# design.net
KiCad netlist of a schematic drawn in Altium Designer
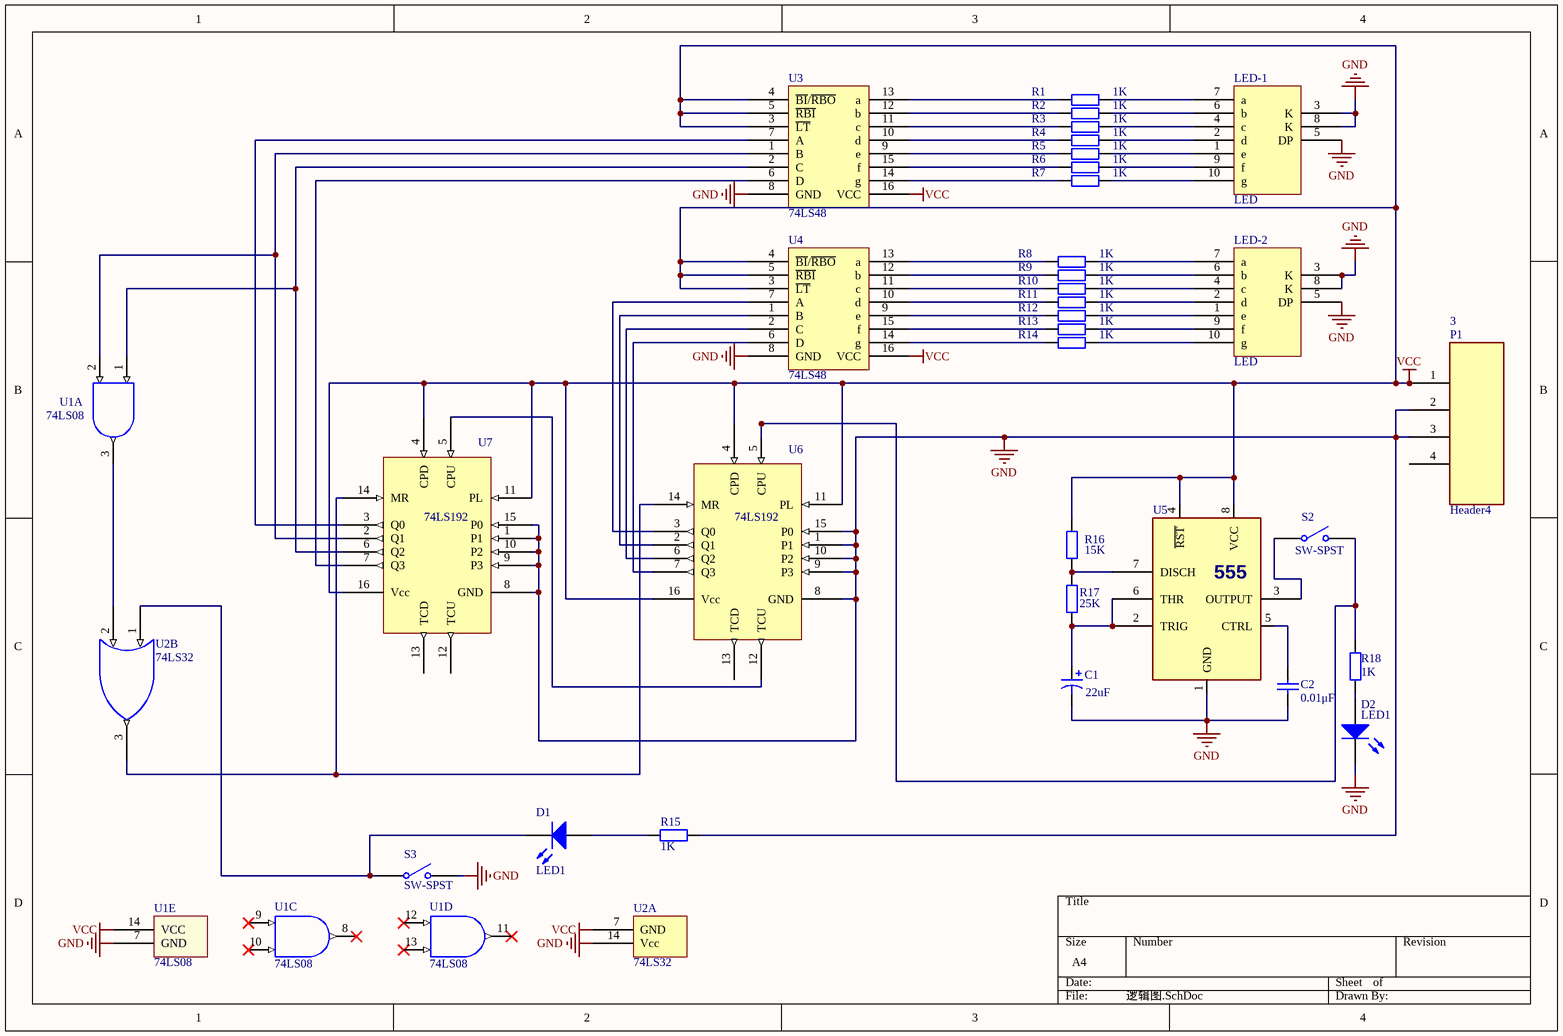
[diagram p0: 逻辑图.SchDoc]

(export (version "E")
  (design (tool "Eeschema 10.0.6"))
  (components
    (comp (ref "3")
      (value "~")
      (footprint "SIP4")
      (description "555 Timer, General-Purpose Single Bipolar Timer")
      (fields (field (name "MANF_P#") "NE555P, NE555PE4") (field (name "MANF") "Texas Instruments"))
      (libsource (lib "ne555") (part "NE555_DIP8"))
    )
    (comp (ref "C1")
      (value "22uF")
      (footprint "RB.2/.4")
      (description "Polarized Capacitor (Radial)")
      (fields (field (name "Comment") "Cap Pol1") (field (name "PUBLISHER") "Altium Limited"))
      (libsource (lib "Miscellaneous Devices") (part "Cap Pol1"))
    )
    (comp (ref "C2")
      (value "0.01μF")
      (footprint "RAD0.2")
      (description "Capacitor")
      (fields (field (name "PUBLISHER") "Altium Limited"))
      (libsource (lib "Miscellaneous Devices") (part "Cap"))
    )
    (comp (ref "D1")
      (value "LED1")
      (footprint "LED-1")
      (description "Typical RED GaAs LED")
      (fields (field (name "PUBLISHER") "Altium Limited"))
      (libsource (lib "Miscellaneous Devices") (part "LED1"))
    )
    (comp (ref "D2")
      (value "LED1")
      (footprint "RAD0.1")
      (description "Typical RED GaAs LED")
      (fields (field (name "PUBLISHER") "Altium Limited"))
      (libsource (lib "Miscellaneous Devices") (part "LED1"))
    )
    (comp (ref "LED-1")
      (value "LED")
      (footprint "DPY_10-SEG_DP(LED)")
      (libsource (lib "Schlib1") (part "LED"))
    )
    (comp (ref "LED-2")
      (value "LED")
      (footprint "DPY_10-SEG_DP(LED)")
      (libsource (lib "Schlib1") (part "LED"))
    )
    (comp (ref "R1")
      (value "1K")
      (footprint "AXIAL-0.4")
      (description "Resistor")
      (fields (field (name "PUBLISHER") "Altium Limited"))
      (libsource (lib "Miscellaneous Devices") (part "Res2"))
    )
    (comp (ref "R2")
      (value "1K")
      (footprint "AXIAL-0.4")
      (description "Resistor")
      (fields (field (name "PUBLISHER") "Altium Limited"))
      (libsource (lib "Miscellaneous Devices") (part "Res2"))
    )
    (comp (ref "R3")
      (value "1K")
      (footprint "AXIAL-0.4")
      (description "Resistor")
      (fields (field (name "PUBLISHER") "Altium Limited"))
      (libsource (lib "Miscellaneous Devices") (part "Res2"))
    )
    (comp (ref "R4")
      (value "1K")
      (footprint "AXIAL-0.4")
      (description "Resistor")
      (fields (field (name "PUBLISHER") "Altium Limited"))
      (libsource (lib "Miscellaneous Devices") (part "Res2"))
    )
    (comp (ref "R5")
      (value "1K")
      (footprint "AXIAL-0.4")
      (description "Resistor")
      (fields (field (name "PUBLISHER") "Altium Limited"))
      (libsource (lib "Miscellaneous Devices") (part "Res2"))
    )
    (comp (ref "R6")
      (value "1K")
      (footprint "AXIAL-0.4")
      (description "Resistor")
      (fields (field (name "PUBLISHER") "Altium Limited"))
      (libsource (lib "Miscellaneous Devices") (part "Res2"))
    )
    (comp (ref "R7")
      (value "1K")
      (footprint "AXIAL-0.4")
      (description "Resistor")
      (fields (field (name "PUBLISHER") "Altium Limited"))
      (libsource (lib "Miscellaneous Devices") (part "Res2"))
    )
    (comp (ref "R8")
      (value "1K")
      (footprint "AXIAL-0.4")
      (description "Resistor")
      (fields (field (name "PUBLISHER") "Altium Limited"))
      (libsource (lib "Miscellaneous Devices") (part "Res2"))
    )
    (comp (ref "R9")
      (value "1K")
      (footprint "AXIAL-0.4")
      (description "Resistor")
      (fields (field (name "PUBLISHER") "Altium Limited"))
      (libsource (lib "Miscellaneous Devices") (part "Res2"))
    )
    (comp (ref "R10")
      (value "1K")
      (footprint "AXIAL-0.4")
      (description "Resistor")
      (fields (field (name "PUBLISHER") "Altium Limited"))
      (libsource (lib "Miscellaneous Devices") (part "Res2"))
    )
    (comp (ref "R11")
      (value "1K")
      (footprint "AXIAL-0.4")
      (description "Resistor")
      (fields (field (name "PUBLISHER") "Altium Limited"))
      (libsource (lib "Miscellaneous Devices") (part "Res2"))
    )
    (comp (ref "R12")
      (value "1K")
      (footprint "AXIAL-0.4")
      (description "Resistor")
      (fields (field (name "PUBLISHER") "Altium Limited"))
      (libsource (lib "Miscellaneous Devices") (part "Res2"))
    )
    (comp (ref "R13")
      (value "1K")
      (footprint "AXIAL-0.4")
      (description "Resistor")
      (fields (field (name "PUBLISHER") "Altium Limited"))
      (libsource (lib "Miscellaneous Devices") (part "Res2"))
    )
    (comp (ref "R14")
      (value "1K")
      (footprint "AXIAL-0.4")
      (description "Resistor")
      (fields (field (name "PUBLISHER") "Altium Limited"))
      (libsource (lib "Miscellaneous Devices") (part "Res2"))
    )
    (comp (ref "R15")
      (value "1K")
      (footprint "AXIAL-0.4")
      (description "Resistor")
      (fields (field (name "PUBLISHER") "Altium Limited"))
      (libsource (lib "") (part "Res2_2"))
    )
    (comp (ref "R16")
      (value "15K")
      (footprint "AXIAL-0.4")
      (description "Resistor")
      (fields (field (name "PUBLISHER") "Altium Limited"))
      (libsource (lib "") (part "Res2_1"))
    )
    (comp (ref "R17")
      (value "25K")
      (footprint "AXIAL-0.4")
      (description "Resistor")
      (fields (field (name "PUBLISHER") "Altium Limited"))
      (libsource (lib "") (part "Res2_1"))
    )
    (comp (ref "R18")
      (value "1K")
      (footprint "AXIAL-0.4")
      (description "Resistor")
      (fields (field (name "PUBLISHER") "Altium Limited"))
      (libsource (lib "") (part "Res2_3"))
    )
    (comp (ref "S2")
      (value "SW-SPST")
      (footprint "SIP3")
      (description "Single-Pole, Single-Throw Switch")
      (fields (field (name "PUBLISHER") "Altium Limited"))
      (libsource (lib "Miscellaneous Devices") (part "SW-SPST"))
    )
    (comp (ref "S3")
      (value "SW-SPST")
      (footprint "SIP3")
      (description "Single-Pole, Single-Throw Switch")
      (fields (field (name "PUBLISHER") "Altium Limited"))
      (libsource (lib "Miscellaneous Devices") (part "SW-SPST"))
    )
    (comp (ref "U1")
      (value "74LS08")
      (footprint "DIP-14")
      (description "Quad 2-Input Positive-AND Gate")
      (libsource (lib "PCB_Project") (part "74LS08"))
    )
    (comp (ref "U2") (value "74LS32") (footprint "DIP-14") (libsource (lib "sw") (part "74LS32")))
    (comp (ref "U3") (value "74LS48") (footprint "DIP-16") (libsource (lib "PCB_Project") (part "74LS48")))
    (comp (ref "U4") (value "74LS48") (footprint "DIP-16") (libsource (lib "PCB_Project") (part "74LS48")))
    (comp (ref "U5")
      (value "~")
      (footprint "DIP-8")
      (description "555 Timer, General-Purpose Single Bipolar Timer")
      (fields (field (name "MANF_P#") "NE555P, NE555PE4") (field (name "MANF") "Texas Instruments"))
      (libsource (lib "") (part "NE555_DIP8_1"))
    )
    (comp (ref "U6") (value "74LS192") (footprint "DIP-16") (libsource (lib "sw") (part "74LS192")))
    (comp (ref "U7") (value "74LS192") (footprint "DIP-16") (libsource (lib "sw") (part "74LS192")))
  )
  (nets
    (net (code "1") (name "GND") (class "Default")
      (node (ref "3") (pin "2") (pintype "passive"))
      (node (ref "3") (pin "3") (pintype "passive"))
      (node (ref "C1") (pin "2") (pinfunction "2_2") (pintype "passive"))
      (node (ref "C2") (pin "1") (pinfunction "1_1") (pintype "passive"))
      (node (ref "D2") (pin "2") (pinfunction "K_2") (pintype "passive"))
      (node (ref "LED-1") (pin "3") (pinfunction "K_3") (pintype "passive"))
      (node (ref "LED-1") (pin "5") (pinfunction "DP_5") (pintype "passive"))
      (node (ref "LED-1") (pin "8") (pinfunction "K_8") (pintype "passive"))
      (node (ref "LED-2") (pin "3") (pinfunction "K_3") (pintype "passive"))
      (node (ref "LED-2") (pin "5") (pinfunction "DP_5") (pintype "passive"))
      (node (ref "LED-2") (pin "8") (pinfunction "K_8") (pintype "passive"))
      (node (ref "R15") (pin "2") (pinfunction "2_2") (pintype "passive"))
      (node (ref "S3") (pin "2") (pinfunction "NO_2") (pintype "passive"))
      (node (ref "U1") (pin "7") (pinfunction "GND_7") (pintype "power_in"))
      (node (ref "U2") (pin "14") (pinfunction "Vcc_14") (pintype "passive"))
      (node (ref "U3") (pin "8") (pinfunction "GND_8") (pintype "passive"))
      (node (ref "U4") (pin "8") (pinfunction "GND_8") (pintype "passive"))
      (node (ref "U5") (pin "1") (pinfunction "GND_1") (pintype "passive"))
      (node (ref "U6") (pin "1") (pinfunction "P1_1") (pintype "input"))
      (node (ref "U6") (pin "10") (pinfunction "P2_10") (pintype "input"))
      (node (ref "U6") (pin "15") (pinfunction "P0_15") (pintype "input"))
      (node (ref "U6") (pin "8") (pinfunction "GND_8") (pintype "passive"))
      (node (ref "U6") (pin "9") (pinfunction "P3_9") (pintype "input"))
      (node (ref "U7") (pin "1") (pinfunction "P1_1") (pintype "input"))
      (node (ref "U7") (pin "10") (pinfunction "P2_10") (pintype "input"))
      (node (ref "U7") (pin "15") (pinfunction "P0_15") (pintype "input"))
      (node (ref "U7") (pin "8") (pinfunction "GND_8") (pintype "passive"))
      (node (ref "U7") (pin "9") (pinfunction "P3_9") (pintype "input"))
    )
    (net (code "2") (name "Net-(D1-A)") (class "Default")
      (node (ref "D1") (pin "1") (pinfunction "A_1") (pintype "passive"))
      (node (ref "R15") (pin "1") (pinfunction "1_1") (pintype "passive"))
    )
    (net (code "3") (name "Net-(D1-K)") (class "Default")
      (node (ref "D1") (pin "2") (pinfunction "K_2") (pintype "passive"))
      (node (ref "S3") (pin "1") (pinfunction "COMMON_1") (pintype "passive"))
      (node (ref "U2") (pin "1") (pinfunction "1A_1") (pintype "input"))
    )
    (net (code "4") (name "Net-(D2-A)") (class "Default")
      (node (ref "D2") (pin "1") (pinfunction "A_1") (pintype "passive"))
      (node (ref "R18") (pin "2") (pinfunction "2_2") (pintype "passive"))
    )
    (net (code "5") (name "Net-(LED-1-a)") (class "Default")
      (node (ref "LED-1") (pin "7") (pinfunction "a_7") (pintype "passive"))
      (node (ref "R1") (pin "1") (pinfunction "1_1") (pintype "passive"))
    )
    (net (code "6") (name "Net-(LED-1-b)") (class "Default")
      (node (ref "LED-1") (pin "6") (pinfunction "b_6") (pintype "passive"))
      (node (ref "R2") (pin "1") (pinfunction "1_1") (pintype "passive"))
    )
    (net (code "7") (name "Net-(LED-1-c)") (class "Default")
      (node (ref "LED-1") (pin "4") (pinfunction "c_4") (pintype "passive"))
      (node (ref "R3") (pin "1") (pinfunction "1_1") (pintype "passive"))
    )
    (net (code "8") (name "Net-(LED-1-d)") (class "Default")
      (node (ref "LED-1") (pin "2") (pinfunction "d_2") (pintype "passive"))
      (node (ref "R4") (pin "1") (pinfunction "1_1") (pintype "passive"))
    )
    (net (code "9") (name "Net-(LED-1-e)") (class "Default")
      (node (ref "LED-1") (pin "1") (pinfunction "e_1") (pintype "passive"))
      (node (ref "R5") (pin "1") (pinfunction "1_1") (pintype "passive"))
    )
    (net (code "10") (name "Net-(LED-1-f)") (class "Default")
      (node (ref "LED-1") (pin "9") (pinfunction "f_9") (pintype "passive"))
      (node (ref "R6") (pin "1") (pinfunction "1_1") (pintype "passive"))
    )
    (net (code "11") (name "Net-(LED-1-g)") (class "Default")
      (node (ref "LED-1") (pin "10") (pinfunction "g_10") (pintype "passive"))
      (node (ref "R7") (pin "1") (pinfunction "1_1") (pintype "passive"))
    )
    (net (code "12") (name "Net-(LED-2-a)") (class "Default")
      (node (ref "LED-2") (pin "7") (pinfunction "a_7") (pintype "passive"))
      (node (ref "R8") (pin "1") (pinfunction "1_1") (pintype "passive"))
    )
    (net (code "13") (name "Net-(LED-2-b)") (class "Default")
      (node (ref "LED-2") (pin "6") (pinfunction "b_6") (pintype "passive"))
      (node (ref "R9") (pin "1") (pinfunction "1_1") (pintype "passive"))
    )
    (net (code "14") (name "Net-(LED-2-c)") (class "Default")
      (node (ref "LED-2") (pin "4") (pinfunction "c_4") (pintype "passive"))
      (node (ref "R10") (pin "1") (pinfunction "1_1") (pintype "passive"))
    )
    (net (code "15") (name "Net-(LED-2-d)") (class "Default")
      (node (ref "LED-2") (pin "2") (pinfunction "d_2") (pintype "passive"))
      (node (ref "R11") (pin "1") (pinfunction "1_1") (pintype "passive"))
    )
    (net (code "16") (name "Net-(LED-2-e)") (class "Default")
      (node (ref "LED-2") (pin "1") (pinfunction "e_1") (pintype "passive"))
      (node (ref "R12") (pin "1") (pinfunction "1_1") (pintype "passive"))
    )
    (net (code "17") (name "Net-(LED-2-f)") (class "Default")
      (node (ref "LED-2") (pin "9") (pinfunction "f_9") (pintype "passive"))
      (node (ref "R13") (pin "1") (pinfunction "1_1") (pintype "passive"))
    )
    (net (code "18") (name "Net-(LED-2-g)") (class "Default")
      (node (ref "LED-2") (pin "10") (pinfunction "g_10") (pintype "passive"))
      (node (ref "R14") (pin "1") (pinfunction "1_1") (pintype "passive"))
    )
    (net (code "19") (name "Net-(S2-COMMON)") (class "Default")
      (node (ref "S2") (pin "1") (pinfunction "COMMON_1") (pintype "passive"))
      (node (ref "U5") (pin "3") (pinfunction "OUTPUT_3") (pintype "passive"))
    )
    (net (code "20") (name "Net-(S2-NO)") (class "Default")
      (node (ref "R18") (pin "1") (pinfunction "1_1") (pintype "passive"))
      (node (ref "S2") (pin "2") (pinfunction "NO_2") (pintype "passive"))
      (node (ref "U6") (pin "5") (pinfunction "CPU_5") (pintype "input"))
    )
    (net (code "21") (name "Net-(U1A-A)") (class "Default")
      (node (ref "U1") (pin "1") (pinfunction "A_1") (pintype "input"))
      (node (ref "U3") (pin "2") (pinfunction "C_2") (pintype "passive"))
      (node (ref "U7") (pin "6") (pinfunction "Q2_6") (pintype "output"))
    )
    (net (code "22") (name "Net-(U1A-B)") (class "Default")
      (node (ref "U1") (pin "2") (pinfunction "B_2") (pintype "input"))
      (node (ref "U3") (pin "1") (pinfunction "B_1") (pintype "passive"))
      (node (ref "U7") (pin "2") (pinfunction "Q1_2") (pintype "output"))
    )
    (net (code "23") (name "Net-(U1A-Y)") (class "Default")
      (node (ref "U1") (pin "3") (pinfunction "Y_3") (pintype "output"))
      (node (ref "U2") (pin "2") (pinfunction "1B_2") (pintype "input"))
    )
    (net (code "24") (name "Net-(U2B-1Y)") (class "Default")
      (node (ref "U2") (pin "3") (pinfunction "1Y_3") (pintype "output"))
      (node (ref "U6") (pin "14") (pinfunction "MR_14") (pintype "input"))
      (node (ref "U7") (pin "14") (pinfunction "MR_14") (pintype "input"))
    )
    (net (code "25") (name "Net-(U3-A)") (class "Default")
      (node (ref "U3") (pin "7") (pinfunction "A_7") (pintype "passive"))
      (node (ref "U7") (pin "3") (pinfunction "Q0_3") (pintype "output"))
    )
    (net (code "26") (name "Net-(U3-D)") (class "Default")
      (node (ref "U3") (pin "6") (pinfunction "D_6") (pintype "passive"))
      (node (ref "U7") (pin "7") (pinfunction "Q3_7") (pintype "output"))
    )
    (net (code "27") (name "Net-(U3-a)") (class "Default")
      (node (ref "R1") (pin "2") (pinfunction "2_2") (pintype "passive"))
      (node (ref "U3") (pin "13") (pinfunction "a_13") (pintype "passive"))
    )
    (net (code "28") (name "Net-(U3-b)") (class "Default")
      (node (ref "R2") (pin "2") (pinfunction "2_2") (pintype "passive"))
      (node (ref "U3") (pin "12") (pinfunction "b_12") (pintype "passive"))
    )
    (net (code "29") (name "Net-(U3-c)") (class "Default")
      (node (ref "R3") (pin "2") (pinfunction "2_2") (pintype "passive"))
      (node (ref "U3") (pin "11") (pinfunction "c_11") (pintype "passive"))
    )
    (net (code "30") (name "Net-(U3-d)") (class "Default")
      (node (ref "R4") (pin "2") (pinfunction "2_2") (pintype "passive"))
      (node (ref "U3") (pin "10") (pinfunction "d_10") (pintype "passive"))
    )
    (net (code "31") (name "Net-(U3-e)") (class "Default")
      (node (ref "R5") (pin "2") (pinfunction "2_2") (pintype "passive"))
      (node (ref "U3") (pin "9") (pinfunction "e_9") (pintype "passive"))
    )
    (net (code "32") (name "Net-(U3-f)") (class "Default")
      (node (ref "R6") (pin "2") (pinfunction "2_2") (pintype "passive"))
      (node (ref "U3") (pin "15") (pinfunction "f_15") (pintype "passive"))
    )
    (net (code "33") (name "Net-(U3-g)") (class "Default")
      (node (ref "R7") (pin "2") (pinfunction "2_2") (pintype "passive"))
      (node (ref "U3") (pin "14") (pinfunction "g_14") (pintype "passive"))
    )
    (net (code "34") (name "Net-(U4-A)") (class "Default")
      (node (ref "U4") (pin "7") (pinfunction "A_7") (pintype "passive"))
      (node (ref "U6") (pin "3") (pinfunction "Q0_3") (pintype "output"))
    )
    (net (code "35") (name "Net-(U4-B)") (class "Default")
      (node (ref "U4") (pin "1") (pinfunction "B_1") (pintype "passive"))
      (node (ref "U6") (pin "2") (pinfunction "Q1_2") (pintype "output"))
    )
    (net (code "36") (name "Net-(U4-C)") (class "Default")
      (node (ref "U4") (pin "2") (pinfunction "C_2") (pintype "passive"))
      (node (ref "U6") (pin "6") (pinfunction "Q2_6") (pintype "output"))
    )
    (net (code "37") (name "Net-(U4-D)") (class "Default")
      (node (ref "U4") (pin "6") (pinfunction "D_6") (pintype "passive"))
      (node (ref "U6") (pin "7") (pinfunction "Q3_7") (pintype "output"))
    )
    (net (code "38") (name "Net-(U4-a)") (class "Default")
      (node (ref "R8") (pin "2") (pinfunction "2_2") (pintype "passive"))
      (node (ref "U4") (pin "13") (pinfunction "a_13") (pintype "passive"))
    )
    (net (code "39") (name "Net-(U4-b)") (class "Default")
      (node (ref "R9") (pin "2") (pinfunction "2_2") (pintype "passive"))
      (node (ref "U4") (pin "12") (pinfunction "b_12") (pintype "passive"))
    )
    (net (code "40") (name "Net-(U4-c)") (class "Default")
      (node (ref "R10") (pin "2") (pinfunction "2_2") (pintype "passive"))
      (node (ref "U4") (pin "11") (pinfunction "c_11") (pintype "passive"))
    )
    (net (code "41") (name "Net-(U4-d)") (class "Default")
      (node (ref "R11") (pin "2") (pinfunction "2_2") (pintype "passive"))
      (node (ref "U4") (pin "10") (pinfunction "d_10") (pintype "passive"))
    )
    (net (code "42") (name "Net-(U4-e)") (class "Default")
      (node (ref "R12") (pin "2") (pinfunction "2_2") (pintype "passive"))
      (node (ref "U4") (pin "9") (pinfunction "e_9") (pintype "passive"))
    )
    (net (code "43") (name "Net-(U4-f)") (class "Default")
      (node (ref "R13") (pin "2") (pinfunction "2_2") (pintype "passive"))
      (node (ref "U4") (pin "15") (pinfunction "f_15") (pintype "passive"))
    )
    (net (code "44") (name "Net-(U4-g)") (class "Default")
      (node (ref "R14") (pin "2") (pinfunction "2_2") (pintype "passive"))
      (node (ref "U4") (pin "14") (pinfunction "g_14") (pintype "passive"))
    )
    (net (code "45") (name "Net-(U5-CTRL)") (class "Default")
      (node (ref "C2") (pin "2") (pinfunction "2_2") (pintype "passive"))
      (node (ref "U5") (pin "5") (pinfunction "CTRL_5") (pintype "passive"))
    )
    (net (code "46") (name "Net-(U5-DISCH)") (class "Default")
      (node (ref "R16") (pin "1") (pinfunction "1_1") (pintype "passive"))
      (node (ref "R17") (pin "2") (pinfunction "2_2") (pintype "passive"))
      (node (ref "U5") (pin "7") (pinfunction "DISCH_7") (pintype "passive"))
    )
    (net (code "47") (name "Net-(U5-THR)") (class "Default")
      (node (ref "C1") (pin "1") (pinfunction "1_1") (pintype "passive"))
      (node (ref "R17") (pin "1") (pinfunction "1_1") (pintype "passive"))
      (node (ref "U5") (pin "2") (pinfunction "TRIG_2") (pintype "passive"))
      (node (ref "U5") (pin "6") (pinfunction "THR_6") (pintype "passive"))
    )
    (net (code "48") (name "Net-(U6-TCU)") (class "Default")
      (node (ref "U6") (pin "12") (pinfunction "TCU_12") (pintype "output"))
      (node (ref "U7") (pin "5") (pinfunction "CPU_5") (pintype "input"))
    )
    (net (code "49") (name "VCC") (class "Default")
      (node (ref "3") (pin "1") (pintype "passive"))
      (node (ref "R16") (pin "2") (pinfunction "2_2") (pintype "passive"))
      (node (ref "U1") (pin "14") (pinfunction "VCC_14") (pintype "power_in"))
      (node (ref "U2") (pin "7") (pinfunction "GND_7") (pintype "passive"))
      (node (ref "U3") (pin "16") (pinfunction "VCC_16") (pintype "passive"))
      (node (ref "U3") (pin "3") (pinfunction "~{LT}_3") (pintype "passive"))
      (node (ref "U3") (pin "4") (pinfunction "~{BI}/~{RBO}_4") (pintype "passive"))
      (node (ref "U3") (pin "5") (pinfunction "~{RBI}_5") (pintype "passive"))
      (node (ref "U4") (pin "16") (pinfunction "VCC_16") (pintype "passive"))
      (node (ref "U4") (pin "3") (pinfunction "~{LT}_3") (pintype "passive"))
      (node (ref "U4") (pin "4") (pinfunction "~{BI}/~{RBO}_4") (pintype "passive"))
      (node (ref "U4") (pin "5") (pinfunction "~{RBI}_5") (pintype "passive"))
      (node (ref "U5") (pin "4") (pinfunction "~{RST}_4") (pintype "passive"))
      (node (ref "U5") (pin "8") (pinfunction "VCC_8") (pintype "passive"))
      (node (ref "U6") (pin "11") (pinfunction "PL_11") (pintype "input"))
      (node (ref "U6") (pin "16") (pinfunction "Vcc_16") (pintype "passive"))
      (node (ref "U6") (pin "4") (pinfunction "CPD_4") (pintype "input"))
      (node (ref "U7") (pin "11") (pinfunction "PL_11") (pintype "input"))
      (node (ref "U7") (pin "16") (pinfunction "Vcc_16") (pintype "passive"))
      (node (ref "U7") (pin "4") (pinfunction "CPD_4") (pintype "input"))
    )
    (net (code "50") (name "unconnected-(3-Pad4)") (class "Default")
      (node (ref "3") (pin "4") (pintype "passive"))
    )
    (net (code "51") (name "unconnected-(U1C-A-Pad9)") (class "Default")
      (node (ref "U1") (pin "9") (pinfunction "A_9") (pintype "input+no_connect"))
    )
    (net (code "52") (name "unconnected-(U1C-B-Pad10)") (class "Default")
      (node (ref "U1") (pin "10") (pinfunction "B_10") (pintype "input+no_connect"))
    )
    (net (code "53") (name "unconnected-(U1C-Y-Pad8)") (class "Default")
      (node (ref "U1") (pin "8") (pinfunction "Y_8") (pintype "output+no_connect"))
    )
    (net (code "54") (name "unconnected-(U1D-A-Pad12)") (class "Default")
      (node (ref "U1") (pin "12") (pinfunction "A_12") (pintype "input+no_connect"))
    )
    (net (code "55") (name "unconnected-(U1D-B-Pad13)") (class "Default")
      (node (ref "U1") (pin "13") (pinfunction "B_13") (pintype "input+no_connect"))
    )
    (net (code "56") (name "unconnected-(U1D-Y-Pad11)") (class "Default")
      (node (ref "U1") (pin "11") (pinfunction "Y_11") (pintype "output+no_connect"))
    )
    (net (code "57") (name "unconnected-(U3-Pad8)") (class "Default")
      (node (ref "U3") (pin "8") (pinfunction "8_8") (pintype "passive"))
    )
    (net (code "58") (name "unconnected-(U3-Pad16)") (class "Default")
      (node (ref "U3") (pin "16") (pinfunction "16_16") (pintype "passive"))
    )
    (net (code "59") (name "unconnected-(U4-Pad8)") (class "Default")
      (node (ref "U4") (pin "8") (pinfunction "8_8") (pintype "passive"))
    )
    (net (code "60") (name "unconnected-(U4-Pad16)") (class "Default")
      (node (ref "U4") (pin "16") (pinfunction "16_16") (pintype "passive"))
    )
    (net (code "61") (name "unconnected-(U6-TCD-Pad13)") (class "Default")
      (node (ref "U6") (pin "13") (pinfunction "TCD_13") (pintype "output"))
    )
    (net (code "62") (name "unconnected-(U7-TCD-Pad13)") (class "Default")
      (node (ref "U7") (pin "13") (pinfunction "TCD_13") (pintype "output"))
    )
    (net (code "63") (name "unconnected-(U7-TCU-Pad12)") (class "Default")
      (node (ref "U7") (pin "12") (pinfunction "TCU_12") (pintype "output"))
    )
  )
)
